# XbusTCO_smd.net
KiCad netlist of a schematic drawn in EAGLE
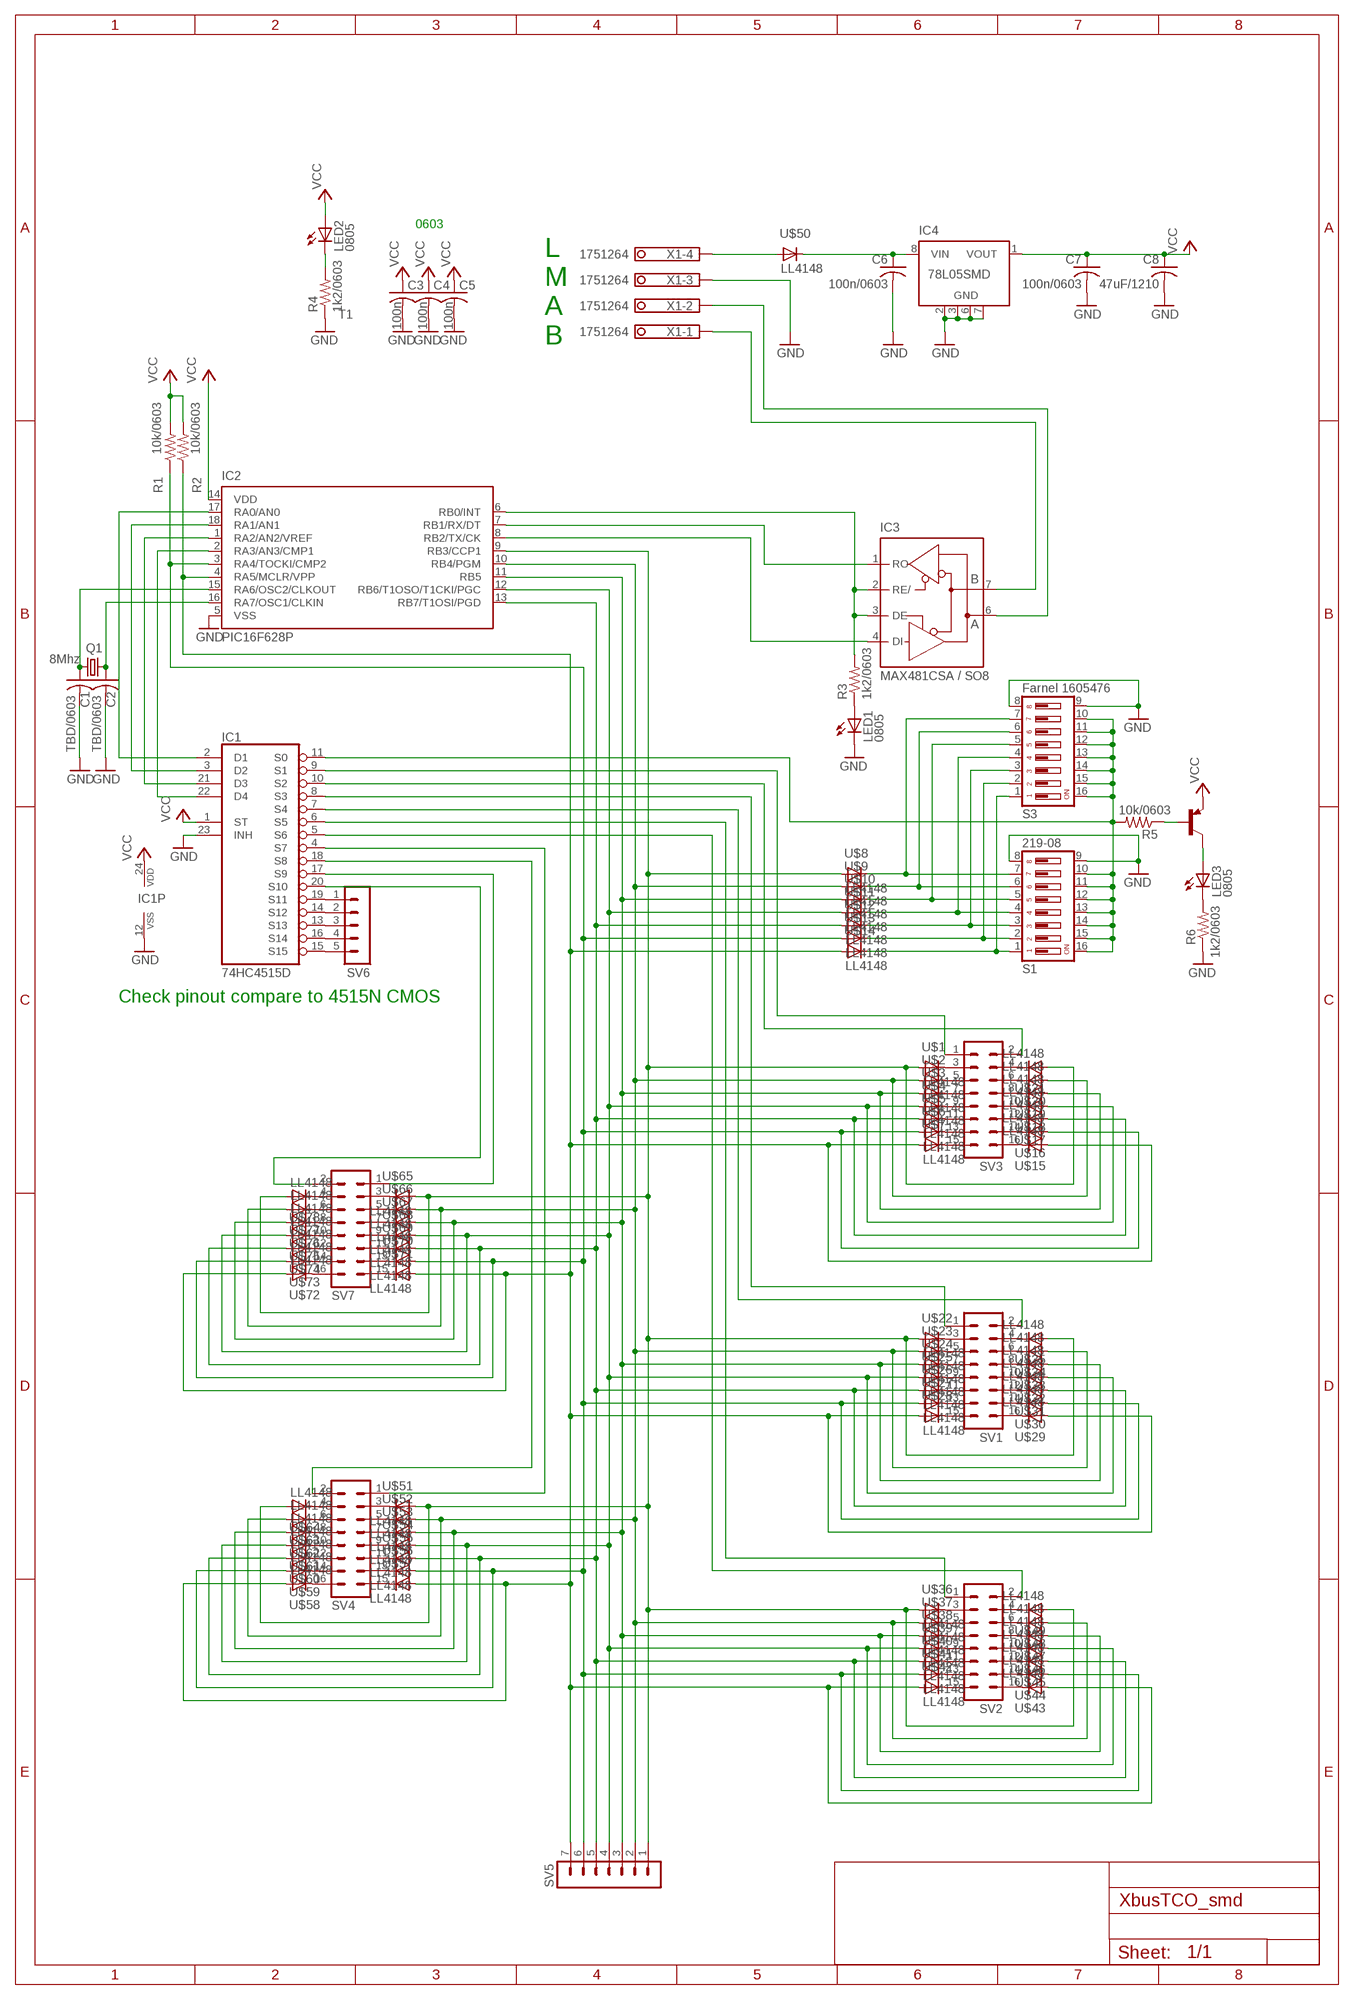
[diagram p0: schematic, sheet 1]

(export (version "E")
  (design (tool "Eeschema 10.0.6"))
  (components
    (comp (ref "C1")
      (value "TBD/0603")
      (footprint "eagle-import:C0603")
      (libsource (lib "eagle-import") (part "C-USC0603"))
    )
    (comp (ref "C2")
      (value "TBD/0603")
      (footprint "eagle-import:C0603")
      (libsource (lib "eagle-import") (part "C-USC0603"))
    )
    (comp (ref "C3")
      (value "100n")
      (footprint "eagle-import:C0603")
      (libsource (lib "eagle-import") (part "C-USC0603"))
    )
    (comp (ref "C4")
      (value "100n")
      (footprint "eagle-import:C0603")
      (libsource (lib "eagle-import") (part "C-USC0603"))
    )
    (comp (ref "C5")
      (value "100n")
      (footprint "eagle-import:C0603")
      (libsource (lib "eagle-import") (part "C-USC0603"))
    )
    (comp (ref "C6")
      (value "100n/0603")
      (footprint "eagle-import:C0603")
      (libsource (lib "eagle-import") (part "C-USC0603"))
    )
    (comp (ref "C7")
      (value "100n/0603")
      (footprint "eagle-import:C0603")
      (libsource (lib "eagle-import") (part "C-USC0603"))
    )
    (comp (ref "C8")
      (value "47uF/1210")
      (footprint "eagle-import:C1210")
      (libsource (lib "eagle-import") (part "C-USC1210"))
    )
    (comp (ref "IC1")
      (value "74HC4515D")
      (footprint "eagle-import:SO24W")
      (libsource (lib "eagle-import") (part "4515D"))
    )
    (comp (ref "IC2")
      (value "PIC16F628P")
      (footprint "eagle-import:DIL18")
      (fields (field (name "MF") "MICROCHIP") (field (name "MPN") "PIC16F628-04I/P"))
      (libsource (lib "eagle-import") (part "PIC16F62P8"))
    )
    (comp (ref "IC3")
      (value "MAX481CSA / SO8")
      (footprint "eagle-import:SO08")
      (fields (field (name "MF") "MAXIM") (field (name "MPN") "MAX481CSA"))
      (libsource (lib "eagle-import") (part "MAX481CSA"))
    )
    (comp (ref "IC4")
      (value "78L05SMD")
      (footprint "eagle-import:SO08")
      (libsource (lib "eagle-import") (part "78LSMD05"))
    )
    (comp (ref "LED1")
      (value "0805")
      (footprint "eagle-import:CHIPLED_0805")
      (libsource (lib "eagle-import") (part "LEDCHIPLED_0805"))
    )
    (comp (ref "LED2")
      (value "0805")
      (footprint "eagle-import:CHIPLED_0805")
      (libsource (lib "eagle-import") (part "LEDCHIPLED_0805"))
    )
    (comp (ref "LED3")
      (value "0805")
      (footprint "eagle-import:CHIPLED_0805")
      (libsource (lib "eagle-import") (part "LEDCHIPLED_0805"))
    )
    (comp (ref "Q1")
      (value "8Mhz")
      (footprint "eagle-import:HC49U70")
      (libsource (lib "eagle-import") (part "CRYSTALHC49U70"))
    )
    (comp (ref "R1")
      (value "10k/0603")
      (footprint "eagle-import:R0603")
      (libsource (lib "eagle-import") (part "R-US_R0603"))
    )
    (comp (ref "R2")
      (value "10k/0603")
      (footprint "eagle-import:R0603")
      (libsource (lib "eagle-import") (part "R-US_R0603"))
    )
    (comp (ref "R3")
      (value "1k2/0603")
      (footprint "eagle-import:R0603")
      (libsource (lib "eagle-import") (part "R-US_R0603"))
    )
    (comp (ref "R4")
      (value "1k2/0603")
      (footprint "eagle-import:R0603")
      (libsource (lib "eagle-import") (part "R-US_R0603"))
    )
    (comp (ref "R5")
      (value "10k/0603")
      (footprint "eagle-import:R0603")
      (libsource (lib "eagle-import") (part "R-US_R0603"))
    )
    (comp (ref "R6")
      (value "1k2/0603")
      (footprint "eagle-import:R0603")
      (libsource (lib "eagle-import") (part "R-US_R0603"))
    )
    (comp (ref "S1")
      (value "219-08")
      (footprint "eagle-import:CTS-219-08")
      (libsource (lib "eagle-import") (part "219-08"))
    )
    (comp (ref "S3")
      (value "Farnel 1605476")
      (footprint "eagle-import:CTS-219-08J")
      (libsource (lib "eagle-import") (part "219-08J"))
    )
    (comp (ref "SV1")
      (value "MA08-2W")
      (footprint "eagle-import:MA08-2W")
      (libsource (lib "eagle-import") (part "MA08-2W"))
    )
    (comp (ref "SV2")
      (value "MA08-2W")
      (footprint "eagle-import:MA08-2W")
      (libsource (lib "eagle-import") (part "MA08-2W"))
    )
    (comp (ref "SV3")
      (value "MA08-2W")
      (footprint "eagle-import:MA08-2W")
      (libsource (lib "eagle-import") (part "MA08-2W"))
    )
    (comp (ref "SV4")
      (value "MA08-2W")
      (footprint "eagle-import:MA08-2W")
      (libsource (lib "eagle-import") (part "MA08-2W"))
    )
    (comp (ref "SV5")
      (value "MA07-1")
      (footprint "eagle-import:MA07-1")
      (libsource (lib "eagle-import") (part "MA07-1"))
    )
    (comp (ref "SV6")
      (value "MA05-1")
      (footprint "eagle-import:MA05-1")
      (libsource (lib "eagle-import") (part "MA05-1"))
    )
    (comp (ref "SV7")
      (value "MA08-2W")
      (footprint "eagle-import:MA08-2W")
      (libsource (lib "eagle-import") (part "MA08-2W"))
    )
    (comp (ref "T1")
      (value "BC857A-PNP-SOT23-BEC")
      (footprint "eagle-import:SOT23-BEC")
      (libsource (lib "eagle-import") (part "-PNP-SOT23-BECBC857A"))
    )
    (comp (ref "U$1")
      (value "LL4148")
      (footprint "eagle-import:MINIMELF")
      (fields (field (name "MF") "ON Semiconductor"))
      (libsource (lib "eagle-import") (part "LL4148"))
    )
    (comp (ref "U$2")
      (value "LL4148")
      (footprint "eagle-import:MINIMELF")
      (fields (field (name "MF") "ON Semiconductor"))
      (libsource (lib "eagle-import") (part "LL4148"))
    )
    (comp (ref "U$3")
      (value "LL4148")
      (footprint "eagle-import:MINIMELF")
      (fields (field (name "MF") "ON Semiconductor"))
      (libsource (lib "eagle-import") (part "LL4148"))
    )
    (comp (ref "U$4")
      (value "LL4148")
      (footprint "eagle-import:MINIMELF")
      (fields (field (name "MF") "ON Semiconductor"))
      (libsource (lib "eagle-import") (part "LL4148"))
    )
    (comp (ref "U$5")
      (value "LL4148")
      (footprint "eagle-import:MINIMELF")
      (fields (field (name "MF") "ON Semiconductor"))
      (libsource (lib "eagle-import") (part "LL4148"))
    )
    (comp (ref "U$6")
      (value "LL4148")
      (footprint "eagle-import:MINIMELF")
      (fields (field (name "MF") "ON Semiconductor"))
      (libsource (lib "eagle-import") (part "LL4148"))
    )
    (comp (ref "U$7")
      (value "LL4148")
      (footprint "eagle-import:MINIMELF")
      (fields (field (name "MF") "ON Semiconductor"))
      (libsource (lib "eagle-import") (part "LL4148"))
    )
    (comp (ref "U$8")
      (value "LL4148")
      (footprint "eagle-import:MINIMELF")
      (fields (field (name "MF") "ON Semiconductor"))
      (libsource (lib "eagle-import") (part "LL4148"))
    )
    (comp (ref "U$9")
      (value "LL4148")
      (footprint "eagle-import:MINIMELF")
      (fields (field (name "MF") "ON Semiconductor"))
      (libsource (lib "eagle-import") (part "LL4148"))
    )
    (comp (ref "U$10")
      (value "LL4148")
      (footprint "eagle-import:MINIMELF")
      (fields (field (name "MF") "ON Semiconductor"))
      (libsource (lib "eagle-import") (part "LL4148"))
    )
    (comp (ref "U$11")
      (value "LL4148")
      (footprint "eagle-import:MINIMELF")
      (fields (field (name "MF") "ON Semiconductor"))
      (libsource (lib "eagle-import") (part "LL4148"))
    )
    (comp (ref "U$12")
      (value "LL4148")
      (footprint "eagle-import:MINIMELF")
      (fields (field (name "MF") "ON Semiconductor"))
      (libsource (lib "eagle-import") (part "LL4148"))
    )
    (comp (ref "U$13")
      (value "LL4148")
      (footprint "eagle-import:MINIMELF")
      (fields (field (name "MF") "ON Semiconductor"))
      (libsource (lib "eagle-import") (part "LL4148"))
    )
    (comp (ref "U$14")
      (value "LL4148")
      (footprint "eagle-import:MINIMELF")
      (fields (field (name "MF") "ON Semiconductor"))
      (libsource (lib "eagle-import") (part "LL4148"))
    )
    (comp (ref "U$15")
      (value "LL4148")
      (footprint "eagle-import:MINIMELF")
      (fields (field (name "MF") "ON Semiconductor"))
      (libsource (lib "eagle-import") (part "LL4148"))
    )
    (comp (ref "U$16")
      (value "LL4148")
      (footprint "eagle-import:MINIMELF")
      (fields (field (name "MF") "ON Semiconductor"))
      (libsource (lib "eagle-import") (part "LL4148"))
    )
    (comp (ref "U$17")
      (value "LL4148")
      (footprint "eagle-import:MINIMELF")
      (fields (field (name "MF") "ON Semiconductor"))
      (libsource (lib "eagle-import") (part "LL4148"))
    )
    (comp (ref "U$18")
      (value "LL4148")
      (footprint "eagle-import:MINIMELF")
      (fields (field (name "MF") "ON Semiconductor"))
      (libsource (lib "eagle-import") (part "LL4148"))
    )
    (comp (ref "U$19")
      (value "LL4148")
      (footprint "eagle-import:MINIMELF")
      (fields (field (name "MF") "ON Semiconductor"))
      (libsource (lib "eagle-import") (part "LL4148"))
    )
    (comp (ref "U$20")
      (value "LL4148")
      (footprint "eagle-import:MINIMELF")
      (fields (field (name "MF") "ON Semiconductor"))
      (libsource (lib "eagle-import") (part "LL4148"))
    )
    (comp (ref "U$21")
      (value "LL4148")
      (footprint "eagle-import:MINIMELF")
      (fields (field (name "MF") "ON Semiconductor"))
      (libsource (lib "eagle-import") (part "LL4148"))
    )
    (comp (ref "U$22")
      (value "LL4148")
      (footprint "eagle-import:MINIMELF")
      (fields (field (name "MF") "ON Semiconductor"))
      (libsource (lib "eagle-import") (part "LL4148"))
    )
    (comp (ref "U$23")
      (value "LL4148")
      (footprint "eagle-import:MINIMELF")
      (fields (field (name "MF") "ON Semiconductor"))
      (libsource (lib "eagle-import") (part "LL4148"))
    )
    (comp (ref "U$24")
      (value "LL4148")
      (footprint "eagle-import:MINIMELF")
      (fields (field (name "MF") "ON Semiconductor"))
      (libsource (lib "eagle-import") (part "LL4148"))
    )
    (comp (ref "U$25")
      (value "LL4148")
      (footprint "eagle-import:MINIMELF")
      (fields (field (name "MF") "ON Semiconductor"))
      (libsource (lib "eagle-import") (part "LL4148"))
    )
    (comp (ref "U$26")
      (value "LL4148")
      (footprint "eagle-import:MINIMELF")
      (fields (field (name "MF") "ON Semiconductor"))
      (libsource (lib "eagle-import") (part "LL4148"))
    )
    (comp (ref "U$27")
      (value "LL4148")
      (footprint "eagle-import:MINIMELF")
      (fields (field (name "MF") "ON Semiconductor"))
      (libsource (lib "eagle-import") (part "LL4148"))
    )
    (comp (ref "U$28")
      (value "LL4148")
      (footprint "eagle-import:MINIMELF")
      (fields (field (name "MF") "ON Semiconductor"))
      (libsource (lib "eagle-import") (part "LL4148"))
    )
    (comp (ref "U$29")
      (value "LL4148")
      (footprint "eagle-import:MINIMELF")
      (fields (field (name "MF") "ON Semiconductor"))
      (libsource (lib "eagle-import") (part "LL4148"))
    )
    (comp (ref "U$30")
      (value "LL4148")
      (footprint "eagle-import:MINIMELF")
      (fields (field (name "MF") "ON Semiconductor"))
      (libsource (lib "eagle-import") (part "LL4148"))
    )
    (comp (ref "U$31")
      (value "LL4148")
      (footprint "eagle-import:MINIMELF")
      (fields (field (name "MF") "ON Semiconductor"))
      (libsource (lib "eagle-import") (part "LL4148"))
    )
    (comp (ref "U$32")
      (value "LL4148")
      (footprint "eagle-import:MINIMELF")
      (fields (field (name "MF") "ON Semiconductor"))
      (libsource (lib "eagle-import") (part "LL4148"))
    )
    (comp (ref "U$33")
      (value "LL4148")
      (footprint "eagle-import:MINIMELF")
      (fields (field (name "MF") "ON Semiconductor"))
      (libsource (lib "eagle-import") (part "LL4148"))
    )
    (comp (ref "U$34")
      (value "LL4148")
      (footprint "eagle-import:MINIMELF")
      (fields (field (name "MF") "ON Semiconductor"))
      (libsource (lib "eagle-import") (part "LL4148"))
    )
    (comp (ref "U$35")
      (value "LL4148")
      (footprint "eagle-import:MINIMELF")
      (fields (field (name "MF") "ON Semiconductor"))
      (libsource (lib "eagle-import") (part "LL4148"))
    )
    (comp (ref "U$36")
      (value "LL4148")
      (footprint "eagle-import:MINIMELF")
      (fields (field (name "MF") "ON Semiconductor"))
      (libsource (lib "eagle-import") (part "LL4148"))
    )
    (comp (ref "U$37")
      (value "LL4148")
      (footprint "eagle-import:MINIMELF")
      (fields (field (name "MF") "ON Semiconductor"))
      (libsource (lib "eagle-import") (part "LL4148"))
    )
    (comp (ref "U$38")
      (value "LL4148")
      (footprint "eagle-import:MINIMELF")
      (fields (field (name "MF") "ON Semiconductor"))
      (libsource (lib "eagle-import") (part "LL4148"))
    )
    (comp (ref "U$39")
      (value "LL4148")
      (footprint "eagle-import:MINIMELF")
      (fields (field (name "MF") "ON Semiconductor"))
      (libsource (lib "eagle-import") (part "LL4148"))
    )
    (comp (ref "U$40")
      (value "LL4148")
      (footprint "eagle-import:MINIMELF")
      (fields (field (name "MF") "ON Semiconductor"))
      (libsource (lib "eagle-import") (part "LL4148"))
    )
    (comp (ref "U$41")
      (value "LL4148")
      (footprint "eagle-import:MINIMELF")
      (fields (field (name "MF") "ON Semiconductor"))
      (libsource (lib "eagle-import") (part "LL4148"))
    )
    (comp (ref "U$42")
      (value "LL4148")
      (footprint "eagle-import:MINIMELF")
      (fields (field (name "MF") "ON Semiconductor"))
      (libsource (lib "eagle-import") (part "LL4148"))
    )
    (comp (ref "U$43")
      (value "LL4148")
      (footprint "eagle-import:MINIMELF")
      (fields (field (name "MF") "ON Semiconductor"))
      (libsource (lib "eagle-import") (part "LL4148"))
    )
    (comp (ref "U$44")
      (value "LL4148")
      (footprint "eagle-import:MINIMELF")
      (fields (field (name "MF") "ON Semiconductor"))
      (libsource (lib "eagle-import") (part "LL4148"))
    )
    (comp (ref "U$45")
      (value "LL4148")
      (footprint "eagle-import:MINIMELF")
      (fields (field (name "MF") "ON Semiconductor"))
      (libsource (lib "eagle-import") (part "LL4148"))
    )
    (comp (ref "U$46")
      (value "LL4148")
      (footprint "eagle-import:MINIMELF")
      (fields (field (name "MF") "ON Semiconductor"))
      (libsource (lib "eagle-import") (part "LL4148"))
    )
    (comp (ref "U$47")
      (value "LL4148")
      (footprint "eagle-import:MINIMELF")
      (fields (field (name "MF") "ON Semiconductor"))
      (libsource (lib "eagle-import") (part "LL4148"))
    )
    (comp (ref "U$48")
      (value "LL4148")
      (footprint "eagle-import:MINIMELF")
      (fields (field (name "MF") "ON Semiconductor"))
      (libsource (lib "eagle-import") (part "LL4148"))
    )
    (comp (ref "U$49")
      (value "LL4148")
      (footprint "eagle-import:MINIMELF")
      (fields (field (name "MF") "ON Semiconductor"))
      (libsource (lib "eagle-import") (part "LL4148"))
    )
    (comp (ref "U$50")
      (value "LL4148")
      (footprint "eagle-import:MINIMELF")
      (fields (field (name "MF") "ON Semiconductor"))
      (libsource (lib "eagle-import") (part "LL4148"))
    )
    (comp (ref "U$51")
      (value "LL4148")
      (footprint "eagle-import:MINIMELF")
      (fields (field (name "MF") "ON Semiconductor"))
      (libsource (lib "eagle-import") (part "LL4148"))
    )
    (comp (ref "U$52")
      (value "LL4148")
      (footprint "eagle-import:MINIMELF")
      (fields (field (name "MF") "ON Semiconductor"))
      (libsource (lib "eagle-import") (part "LL4148"))
    )
    (comp (ref "U$53")
      (value "LL4148")
      (footprint "eagle-import:MINIMELF")
      (fields (field (name "MF") "ON Semiconductor"))
      (libsource (lib "eagle-import") (part "LL4148"))
    )
    (comp (ref "U$54")
      (value "LL4148")
      (footprint "eagle-import:MINIMELF")
      (fields (field (name "MF") "ON Semiconductor"))
      (libsource (lib "eagle-import") (part "LL4148"))
    )
    (comp (ref "U$55")
      (value "LL4148")
      (footprint "eagle-import:MINIMELF")
      (fields (field (name "MF") "ON Semiconductor"))
      (libsource (lib "eagle-import") (part "LL4148"))
    )
    (comp (ref "U$56")
      (value "LL4148")
      (footprint "eagle-import:MINIMELF")
      (fields (field (name "MF") "ON Semiconductor"))
      (libsource (lib "eagle-import") (part "LL4148"))
    )
    (comp (ref "U$57")
      (value "LL4148")
      (footprint "eagle-import:MINIMELF")
      (fields (field (name "MF") "ON Semiconductor"))
      (libsource (lib "eagle-import") (part "LL4148"))
    )
    (comp (ref "U$58")
      (value "LL4148")
      (footprint "eagle-import:MINIMELF")
      (fields (field (name "MF") "ON Semiconductor"))
      (libsource (lib "eagle-import") (part "LL4148"))
    )
    (comp (ref "U$59")
      (value "LL4148")
      (footprint "eagle-import:MINIMELF")
      (fields (field (name "MF") "ON Semiconductor"))
      (libsource (lib "eagle-import") (part "LL4148"))
    )
    (comp (ref "U$60")
      (value "LL4148")
      (footprint "eagle-import:MINIMELF")
      (fields (field (name "MF") "ON Semiconductor"))
      (libsource (lib "eagle-import") (part "LL4148"))
    )
    (comp (ref "U$61")
      (value "LL4148")
      (footprint "eagle-import:MINIMELF")
      (fields (field (name "MF") "ON Semiconductor"))
      (libsource (lib "eagle-import") (part "LL4148"))
    )
    (comp (ref "U$62")
      (value "LL4148")
      (footprint "eagle-import:MINIMELF")
      (fields (field (name "MF") "ON Semiconductor"))
      (libsource (lib "eagle-import") (part "LL4148"))
    )
    (comp (ref "U$63")
      (value "LL4148")
      (footprint "eagle-import:MINIMELF")
      (fields (field (name "MF") "ON Semiconductor"))
      (libsource (lib "eagle-import") (part "LL4148"))
    )
    (comp (ref "U$64")
      (value "LL4148")
      (footprint "eagle-import:MINIMELF")
      (fields (field (name "MF") "ON Semiconductor"))
      (libsource (lib "eagle-import") (part "LL4148"))
    )
    (comp (ref "U$65")
      (value "LL4148")
      (footprint "eagle-import:MINIMELF")
      (fields (field (name "MF") "ON Semiconductor"))
      (libsource (lib "eagle-import") (part "LL4148"))
    )
    (comp (ref "U$66")
      (value "LL4148")
      (footprint "eagle-import:MINIMELF")
      (fields (field (name "MF") "ON Semiconductor"))
      (libsource (lib "eagle-import") (part "LL4148"))
    )
    (comp (ref "U$67")
      (value "LL4148")
      (footprint "eagle-import:MINIMELF")
      (fields (field (name "MF") "ON Semiconductor"))
      (libsource (lib "eagle-import") (part "LL4148"))
    )
    (comp (ref "U$68")
      (value "LL4148")
      (footprint "eagle-import:MINIMELF")
      (fields (field (name "MF") "ON Semiconductor"))
      (libsource (lib "eagle-import") (part "LL4148"))
    )
    (comp (ref "U$69")
      (value "LL4148")
      (footprint "eagle-import:MINIMELF")
      (fields (field (name "MF") "ON Semiconductor"))
      (libsource (lib "eagle-import") (part "LL4148"))
    )
    (comp (ref "U$70")
      (value "LL4148")
      (footprint "eagle-import:MINIMELF")
      (fields (field (name "MF") "ON Semiconductor"))
      (libsource (lib "eagle-import") (part "LL4148"))
    )
    (comp (ref "U$71")
      (value "LL4148")
      (footprint "eagle-import:MINIMELF")
      (fields (field (name "MF") "ON Semiconductor"))
      (libsource (lib "eagle-import") (part "LL4148"))
    )
    (comp (ref "U$72")
      (value "LL4148")
      (footprint "eagle-import:MINIMELF")
      (fields (field (name "MF") "ON Semiconductor"))
      (libsource (lib "eagle-import") (part "LL4148"))
    )
    (comp (ref "U$73")
      (value "LL4148")
      (footprint "eagle-import:MINIMELF")
      (fields (field (name "MF") "ON Semiconductor"))
      (libsource (lib "eagle-import") (part "LL4148"))
    )
    (comp (ref "U$74")
      (value "LL4148")
      (footprint "eagle-import:MINIMELF")
      (fields (field (name "MF") "ON Semiconductor"))
      (libsource (lib "eagle-import") (part "LL4148"))
    )
    (comp (ref "U$75")
      (value "LL4148")
      (footprint "eagle-import:MINIMELF")
      (fields (field (name "MF") "ON Semiconductor"))
      (libsource (lib "eagle-import") (part "LL4148"))
    )
    (comp (ref "U$76")
      (value "LL4148")
      (footprint "eagle-import:MINIMELF")
      (fields (field (name "MF") "ON Semiconductor"))
      (libsource (lib "eagle-import") (part "LL4148"))
    )
    (comp (ref "U$77")
      (value "LL4148")
      (footprint "eagle-import:MINIMELF")
      (fields (field (name "MF") "ON Semiconductor"))
      (libsource (lib "eagle-import") (part "LL4148"))
    )
    (comp (ref "U$78")
      (value "LL4148")
      (footprint "eagle-import:MINIMELF")
      (fields (field (name "MF") "ON Semiconductor"))
      (libsource (lib "eagle-import") (part "LL4148"))
    )
    (comp (ref "X1")
      (value "1751264")
      (footprint "eagle-import:1751264")
      (libsource (lib "eagle-import") (part "1751264"))
    )
  )
  (nets
    (net (code "1") (name "GND") (class "Default")
      (node (ref "C1") (pin "2") (pinfunction "2_2") (pintype "passive"))
      (node (ref "C2") (pin "2") (pinfunction "2_2") (pintype "passive"))
      (node (ref "C3") (pin "2") (pinfunction "2_2") (pintype "passive"))
      (node (ref "C4") (pin "2") (pinfunction "2_2") (pintype "passive"))
      (node (ref "C5") (pin "2") (pinfunction "2_2") (pintype "passive"))
      (node (ref "C6") (pin "2") (pinfunction "2_2") (pintype "passive"))
      (node (ref "C7") (pin "2") (pinfunction "2_2") (pintype "passive"))
      (node (ref "C8") (pin "2") (pinfunction "2_2") (pintype "passive"))
      (node (ref "IC1") (pin "12") (pinfunction "VSS_12") (pintype "power_in"))
      (node (ref "IC1") (pin "23") (pinfunction "INH_23") (pintype "input"))
      (node (ref "IC2") (pin "5") (pinfunction "VSS_5") (pintype "power_in"))
      (node (ref "IC4") (pin "2") (pinfunction "GND_2") (pintype "power_in"))
      (node (ref "IC4") (pin "3") (pinfunction "GND_3") (pintype "power_in"))
      (node (ref "IC4") (pin "6") (pinfunction "GND_6") (pintype "power_in"))
      (node (ref "IC4") (pin "7") (pinfunction "GND_7") (pintype "power_in"))
      (node (ref "LED1") (pin "C") (pinfunction "C_C") (pintype "passive"))
      (node (ref "R4") (pin "1") (pinfunction "1_1") (pintype "passive"))
      (node (ref "R6") (pin "1") (pinfunction "1_1") (pintype "passive"))
      (node (ref "S1") (pin "8") (pinfunction "8_8") (pintype "passive"))
      (node (ref "S1") (pin "9") (pinfunction "9_9") (pintype "passive"))
      (node (ref "S3") (pin "8") (pinfunction "8_8") (pintype "passive"))
      (node (ref "S3") (pin "9") (pinfunction "9_9") (pintype "passive"))
      (node (ref "X1") (pin "3") (pinfunction "K_3") (pintype "passive"))
    )
    (net (code "2") (name "Net-(IC1A-D1)") (class "Default")
      (node (ref "IC1") (pin "2") (pinfunction "D1_2") (pintype "input"))
      (node (ref "IC2") (pin "17") (pinfunction "RA0/AN0_17") (pintype "bidirectional"))
    )
    (net (code "3") (name "Net-(IC1A-D2)") (class "Default")
      (node (ref "IC1") (pin "3") (pinfunction "D2_3") (pintype "input"))
      (node (ref "IC2") (pin "18") (pinfunction "RA1/AN1_18") (pintype "bidirectional"))
    )
    (net (code "4") (name "Net-(IC1A-D3)") (class "Default")
      (node (ref "IC1") (pin "21") (pinfunction "D3_21") (pintype "input"))
      (node (ref "IC2") (pin "1") (pinfunction "RA2/AN2/VREF_1") (pintype "bidirectional"))
    )
    (net (code "5") (name "Net-(IC1A-D4)") (class "Default")
      (node (ref "IC1") (pin "22") (pinfunction "D4_22") (pintype "input"))
      (node (ref "IC2") (pin "2") (pinfunction "RA3/AN3/CMP1_2") (pintype "bidirectional"))
    )
    (net (code "6") (name "Net-(IC1A-S0)") (class "Default")
      (node (ref "IC1") (pin "11") (pinfunction "S0_11") (pintype "output"))
      (node (ref "R5") (pin "2") (pinfunction "2_2") (pintype "passive"))
      (node (ref "S1") (pin "10") (pinfunction "10_10") (pintype "passive"))
      (node (ref "S1") (pin "11") (pinfunction "11_11") (pintype "passive"))
      (node (ref "S1") (pin "12") (pinfunction "12_12") (pintype "passive"))
      (node (ref "S1") (pin "13") (pinfunction "13_13") (pintype "passive"))
      (node (ref "S1") (pin "14") (pinfunction "14_14") (pintype "passive"))
      (node (ref "S1") (pin "15") (pinfunction "15_15") (pintype "passive"))
      (node (ref "S1") (pin "16") (pinfunction "16_16") (pintype "passive"))
      (node (ref "S3") (pin "10") (pinfunction "10_10") (pintype "passive"))
      (node (ref "S3") (pin "11") (pinfunction "11_11") (pintype "passive"))
      (node (ref "S3") (pin "12") (pinfunction "12_12") (pintype "passive"))
      (node (ref "S3") (pin "13") (pinfunction "13_13") (pintype "passive"))
      (node (ref "S3") (pin "14") (pinfunction "14_14") (pintype "passive"))
      (node (ref "S3") (pin "15") (pinfunction "15_15") (pintype "passive"))
      (node (ref "S3") (pin "16") (pinfunction "16_16") (pintype "passive"))
    )
    (net (code "7") (name "Net-(IC1A-S1)") (class "Default")
      (node (ref "IC1") (pin "9") (pinfunction "S1_9") (pintype "output"))
      (node (ref "SV3") (pin "1") (pinfunction "1_1") (pintype "passive"))
    )
    (net (code "8") (name "Net-(IC1A-S2)") (class "Default")
      (node (ref "IC1") (pin "10") (pinfunction "S2_10") (pintype "output"))
      (node (ref "SV3") (pin "2") (pinfunction "2_2") (pintype "passive"))
    )
    (net (code "9") (name "Net-(IC1A-S3)") (class "Default")
      (node (ref "IC1") (pin "8") (pinfunction "S3_8") (pintype "output"))
      (node (ref "SV1") (pin "1") (pinfunction "1_1") (pintype "passive"))
    )
    (net (code "10") (name "Net-(IC1A-S4)") (class "Default")
      (node (ref "IC1") (pin "7") (pinfunction "S4_7") (pintype "output"))
      (node (ref "SV1") (pin "2") (pinfunction "2_2") (pintype "passive"))
    )
    (net (code "11") (name "Net-(IC1A-S5)") (class "Default")
      (node (ref "IC1") (pin "6") (pinfunction "S5_6") (pintype "output"))
      (node (ref "SV2") (pin "1") (pinfunction "1_1") (pintype "passive"))
    )
    (net (code "12") (name "Net-(IC1A-S6)") (class "Default")
      (node (ref "IC1") (pin "5") (pinfunction "S6_5") (pintype "output"))
      (node (ref "SV2") (pin "2") (pinfunction "2_2") (pintype "passive"))
    )
    (net (code "13") (name "Net-(IC1A-S7)") (class "Default")
      (node (ref "IC1") (pin "4") (pinfunction "S7_4") (pintype "output"))
      (node (ref "SV4") (pin "1") (pinfunction "1_1") (pintype "passive"))
    )
    (net (code "14") (name "Net-(IC1A-S8)") (class "Default")
      (node (ref "IC1") (pin "18") (pinfunction "S8_18") (pintype "output"))
      (node (ref "SV4") (pin "2") (pinfunction "2_2") (pintype "passive"))
    )
    (net (code "15") (name "Net-(IC1A-S9)") (class "Default")
      (node (ref "IC1") (pin "17") (pinfunction "S9_17") (pintype "output"))
      (node (ref "SV7") (pin "1") (pinfunction "1_1") (pintype "passive"))
    )
    (net (code "16") (name "Net-(IC1A-S10)") (class "Default")
      (node (ref "IC1") (pin "20") (pinfunction "S10_20") (pintype "output"))
      (node (ref "SV7") (pin "2") (pinfunction "2_2") (pintype "passive"))
    )
    (net (code "17") (name "Net-(IC1A-S11)") (class "Default")
      (node (ref "IC1") (pin "19") (pinfunction "S11_19") (pintype "output"))
      (node (ref "SV6") (pin "1") (pinfunction "1_1") (pintype "passive"))
    )
    (net (code "18") (name "Net-(IC1A-S12)") (class "Default")
      (node (ref "IC1") (pin "14") (pinfunction "S12_14") (pintype "output"))
      (node (ref "SV6") (pin "2") (pinfunction "2_2") (pintype "passive"))
    )
    (net (code "19") (name "Net-(IC1A-S13)") (class "Default")
      (node (ref "IC1") (pin "13") (pinfunction "S13_13") (pintype "output"))
      (node (ref "SV6") (pin "3") (pinfunction "3_3") (pintype "passive"))
    )
    (net (code "20") (name "Net-(IC1A-S14)") (class "Default")
      (node (ref "IC1") (pin "16") (pinfunction "S14_16") (pintype "output"))
      (node (ref "SV6") (pin "4") (pinfunction "4_4") (pintype "passive"))
    )
    (net (code "21") (name "Net-(IC1A-S15)") (class "Default")
      (node (ref "IC1") (pin "15") (pinfunction "S15_15") (pintype "output"))
      (node (ref "SV6") (pin "5") (pinfunction "5_5") (pintype "passive"))
    )
    (net (code "22") (name "Net-(IC2-RA4{slash}TOCKI{slash}CMP2)") (class "Default")
      (node (ref "IC2") (pin "3") (pinfunction "RA4/TOCKI/CMP2_3") (pintype "bidirectional"))
      (node (ref "R1") (pin "1") (pinfunction "1_1") (pintype "passive"))
      (node (ref "SV5") (pin "6") (pinfunction "6_6") (pintype "passive"))
      (node (ref "U$13") (pin "A") (pinfunction "A_A") (pintype "passive"))
      (node (ref "U$16") (pin "A") (pinfunction "A_A") (pintype "passive"))
      (node (ref "U$27") (pin "A") (pinfunction "A_A") (pintype "passive"))
      (node (ref "U$30") (pin "A") (pinfunction "A_A") (pintype "passive"))
      (node (ref "U$41") (pin "A") (pinfunction "A_A") (pintype "passive"))
      (node (ref "U$44") (pin "A") (pinfunction "A_A") (pintype "passive"))
      (node (ref "U$56") (pin "A") (pinfunction "A_A") (pintype "passive"))
      (node (ref "U$59") (pin "A") (pinfunction "A_A") (pintype "passive"))
      (node (ref "U$6") (pin "A") (pinfunction "A_A") (pintype "passive"))
      (node (ref "U$70") (pin "A") (pinfunction "A_A") (pintype "passive"))
      (node (ref "U$73") (pin "A") (pinfunction "A_A") (pintype "passive"))
    )
    (net (code "23") (name "Net-(IC2-RA5{slash}MCLR{slash}VPP)") (class "Default")
      (node (ref "IC2") (pin "4") (pinfunction "RA5/MCLR/VPP_4") (pintype "bidirectional"))
      (node (ref "R2") (pin "1") (pinfunction "1_1") (pintype "passive"))
      (node (ref "SV5") (pin "7") (pinfunction "7_7") (pintype "passive"))
      (node (ref "U$14") (pin "A") (pinfunction "A_A") (pintype "passive"))
      (node (ref "U$15") (pin "A") (pinfunction "A_A") (pintype "passive"))
      (node (ref "U$28") (pin "A") (pinfunction "A_A") (pintype "passive"))
      (node (ref "U$29") (pin "A") (pinfunction "A_A") (pintype "passive"))
      (node (ref "U$42") (pin "A") (pinfunction "A_A") (pintype "passive"))
      (node (ref "U$43") (pin "A") (pinfunction "A_A") (pintype "passive"))
      (node (ref "U$57") (pin "A") (pinfunction "A_A") (pintype "passive"))
      (node (ref "U$58") (pin "A") (pinfunction "A_A") (pintype "passive"))
      (node (ref "U$7") (pin "A") (pinfunction "A_A") (pintype "passive"))
      (node (ref "U$71") (pin "A") (pinfunction "A_A") (pintype "passive"))
      (node (ref "U$72") (pin "A") (pinfunction "A_A") (pintype "passive"))
    )
    (net (code "24") (name "Net-(IC2-RA6{slash}OSC2{slash}CLKOUT)") (class "Default")
      (node (ref "C1") (pin "1") (pinfunction "1_1") (pintype "passive"))
      (node (ref "IC2") (pin "15") (pinfunction "RA6/OSC2/CLKOUT_15") (pintype "bidirectional"))
      (node (ref "Q1") (pin "2") (pinfunction "2_2") (pintype "passive"))
    )
    (net (code "25") (name "Net-(IC2-RA7{slash}OSC1{slash}CLKIN)") (class "Default")
      (node (ref "C2") (pin "1") (pinfunction "1_1") (pintype "passive"))
      (node (ref "IC2") (pin "16") (pinfunction "RA7/OSC1/CLKIN_16") (pintype "bidirectional"))
      (node (ref "Q1") (pin "1") (pinfunction "1_1") (pintype "passive"))
    )
    (net (code "26") (name "Net-(IC2-RB0{slash}INT)") (class "Default")
      (node (ref "IC2") (pin "6") (pinfunction "RB0/INT_6") (pintype "bidirectional"))
      (node (ref "IC3") (pin "2") (pinfunction "RE/_2") (pintype "input"))
      (node (ref "IC3") (pin "3") (pinfunction "DE_3") (pintype "input"))
      (node (ref "R3") (pin "2") (pinfunction "2_2") (pintype "passive"))
    )
    (net (code "27") (name "Net-(IC2-RB1{slash}RX{slash}DT)") (class "Default")
      (node (ref "IC2") (pin "7") (pinfunction "RB1/RX/DT_7") (pintype "bidirectional"))
      (node (ref "IC3") (pin "1") (pinfunction "RO_1") (pintype "output"))
    )
    (net (code "28") (name "Net-(IC2-RB2{slash}TX{slash}CK)") (class "Default")
      (node (ref "IC2") (pin "8") (pinfunction "RB2/TX/CK_8") (pintype "bidirectional"))
      (node (ref "IC3") (pin "4") (pinfunction "DI_4") (pintype "input"))
    )
    (net (code "29") (name "Net-(IC2-RB3{slash}CCP1)") (class "Default")
      (node (ref "IC2") (pin "9") (pinfunction "RB3/CCP1_9") (pintype "bidirectional"))
      (node (ref "SV5") (pin "1") (pinfunction "1_1") (pintype "passive"))
      (node (ref "U$1") (pin "A") (pinfunction "A_A") (pintype "passive"))
      (node (ref "U$21") (pin "A") (pinfunction "A_A") (pintype "passive"))
      (node (ref "U$22") (pin "A") (pinfunction "A_A") (pintype "passive"))
      (node (ref "U$35") (pin "A") (pinfunction "A_A") (pintype "passive"))
      (node (ref "U$36") (pin "A") (pinfunction "A_A") (pintype "passive"))
      (node (ref "U$49") (pin "A") (pinfunction "A_A") (pintype "passive"))
      (node (ref "U$51") (pin "A") (pinfunction "A_A") (pintype "passive"))
      (node (ref "U$64") (pin "A") (pinfunction "A_A") (pintype "passive"))
      (node (ref "U$65") (pin "A") (pinfunction "A_A") (pintype "passive"))
      (node (ref "U$78") (pin "A") (pinfunction "A_A") (pintype "passive"))
      (node (ref "U$8") (pin "A") (pinfunction "A_A") (pintype "passive"))
    )
    (net (code "30") (name "Net-(IC2-RB4{slash}PGM)") (class "Default")
      (node (ref "IC2") (pin "10") (pinfunction "RB4/PGM_10") (pintype "bidirectional"))
      (node (ref "SV5") (pin "2") (pinfunction "2_2") (pintype "passive"))
      (node (ref "U$2") (pin "A") (pinfunction "A_A") (pintype "passive"))
      (node (ref "U$20") (pin "A") (pinfunction "A_A") (pintype "passive"))
      (node (ref "U$23") (pin "A") (pinfunction "A_A") (pintype "passive"))
      (node (ref "U$34") (pin "A") (pinfunction "A_A") (pintype "passive"))
      (node (ref "U$37") (pin "A") (pinfunction "A_A") (pintype "passive"))
      (node (ref "U$48") (pin "A") (pinfunction "A_A") (pintype "passive"))
      (node (ref "U$52") (pin "A") (pinfunction "A_A") (pintype "passive"))
      (node (ref "U$63") (pin "A") (pinfunction "A_A") (pintype "passive"))
      (node (ref "U$66") (pin "A") (pinfunction "A_A") (pintype "passive"))
      (node (ref "U$77") (pin "A") (pinfunction "A_A") (pintype "passive"))
      (node (ref "U$9") (pin "A") (pinfunction "A_A") (pintype "passive"))
    )
    (net (code "31") (name "Net-(IC2-RB5)") (class "Default")
      (node (ref "IC2") (pin "11") (pinfunction "RB5_11") (pintype "bidirectional"))
      (node (ref "SV5") (pin "3") (pinfunction "3_3") (pintype "passive"))
      (node (ref "U$10") (pin "A") (pinfunction "A_A") (pintype "passive"))
      (node (ref "U$19") (pin "A") (pinfunction "A_A") (pintype "passive"))
      (node (ref "U$24") (pin "A") (pinfunction "A_A") (pintype "passive"))
      (node (ref "U$3") (pin "A") (pinfunction "A_A") (pintype "passive"))
      (node (ref "U$33") (pin "A") (pinfunction "A_A") (pintype "passive"))
      (node (ref "U$38") (pin "A") (pinfunction "A_A") (pintype "passive"))
      (node (ref "U$47") (pin "A") (pinfunction "A_A") (pintype "passive"))
      (node (ref "U$53") (pin "A") (pinfunction "A_A") (pintype "passive"))
      (node (ref "U$62") (pin "A") (pinfunction "A_A") (pintype "passive"))
      (node (ref "U$67") (pin "A") (pinfunction "A_A") (pintype "passive"))
      (node (ref "U$76") (pin "A") (pinfunction "A_A") (pintype "passive"))
    )
    (net (code "32") (name "Net-(IC2-RB6{slash}T1OSO{slash}T1CKI{slash}PGC)") (class "Default")
      (node (ref "IC2") (pin "12") (pinfunction "RB6/T1OSO/T1CKI/PGC_12") (pintype "bidirectional"))
      (node (ref "SV5") (pin "4") (pinfunction "4_4") (pintype "passive"))
      (node (ref "U$11") (pin "A") (pinfunction "A_A") (pintype "passive"))
      (node (ref "U$18") (pin "A") (pinfunction "A_A") (pintype "passive"))
      (node (ref "U$25") (pin "A") (pinfunction "A_A") (pintype "passive"))
      (node (ref "U$32") (pin "A") (pinfunction "A_A") (pintype "passive"))
      (node (ref "U$39") (pin "A") (pinfunction "A_A") (pintype "passive"))
      (node (ref "U$4") (pin "A") (pinfunction "A_A") (pintype "passive"))
      (node (ref "U$46") (pin "A") (pinfunction "A_A") (pintype "passive"))
      (node (ref "U$54") (pin "A") (pinfunction "A_A") (pintype "passive"))
      (node (ref "U$61") (pin "A") (pinfunction "A_A") (pintype "passive"))
      (node (ref "U$68") (pin "A") (pinfunction "A_A") (pintype "passive"))
      (node (ref "U$75") (pin "A") (pinfunction "A_A") (pintype "passive"))
    )
    (net (code "33") (name "Net-(IC2-RB7{slash}T1OSI{slash}PGD)") (class "Default")
      (node (ref "IC2") (pin "13") (pinfunction "RB7/T1OSI/PGD_13") (pintype "bidirectional"))
      (node (ref "SV5") (pin "5") (pinfunction "5_5") (pintype "passive"))
      (node (ref "U$12") (pin "A") (pinfunction "A_A") (pintype "passive"))
      (node (ref "U$17") (pin "A") (pinfunction "A_A") (pintype "passive"))
      (node (ref "U$26") (pin "A") (pinfunction "A_A") (pintype "passive"))
      (node (ref "U$31") (pin "A") (pinfunction "A_A") (pintype "passive"))
      (node (ref "U$40") (pin "A") (pinfunction "A_A") (pintype "passive"))
      (node (ref "U$45") (pin "A") (pinfunction "A_A") (pintype "passive"))
      (node (ref "U$5") (pin "A") (pinfunction "A_A") (pintype "passive"))
      (node (ref "U$55") (pin "A") (pinfunction "A_A") (pintype "passive"))
      (node (ref "U$60") (pin "A") (pinfunction "A_A") (pintype "passive"))
      (node (ref "U$69") (pin "A") (pinfunction "A_A") (pintype "passive"))
      (node (ref "U$74") (pin "A") (pinfunction "A_A") (pintype "passive"))
    )
    (net (code "34") (name "Net-(IC3A-A)") (class "Default")
      (node (ref "IC3") (pin "6") (pinfunction "A_6") (pintype "passive"))
      (node (ref "X1") (pin "2") (pinfunction "K_2") (pintype "passive"))
    )
    (net (code "35") (name "Net-(IC3A-B)") (class "Default")
      (node (ref "IC3") (pin "7") (pinfunction "B_7") (pintype "passive"))
      (node (ref "X1") (pin "1") (pinfunction "K_1") (pintype "passive"))
    )
    (net (code "36") (name "Net-(IC4A-VIN)") (class "Default")
      (node (ref "C6") (pin "1") (pinfunction "1_1") (pintype "passive"))
      (node (ref "IC4") (pin "8") (pinfunction "VIN_8") (pintype "passive"))
      (node (ref "U$50") (pin "C") (pinfunction "C_C") (pintype "passive"))
    )
    (net (code "37") (name "Net-(LED1-PadA)") (class "Default")
      (node (ref "LED1") (pin "A") (pinfunction "A_A") (pintype "passive"))
      (node (ref "R3") (pin "1") (pinfunction "1_1") (pintype "passive"))
    )
    (net (code "38") (name "Net-(LED2-PadC)") (class "Default")
      (node (ref "LED2") (pin "C") (pinfunction "C_C") (pintype "passive"))
      (node (ref "R4") (pin "2") (pinfunction "2_2") (pintype "passive"))
    )
    (net (code "39") (name "Net-(LED3-PadA)") (class "Default")
      (node (ref "LED3") (pin "A") (pinfunction "A_A") (pintype "passive"))
      (node (ref "T1") (pin "C") (pinfunction "C_C") (pintype "passive"))
    )
    (net (code "40") (name "Net-(LED3-PadC)") (class "Default")
      (node (ref "LED3") (pin "C") (pinfunction "C_C") (pintype "passive"))
      (node (ref "R6") (pin "2") (pinfunction "2_2") (pintype "passive"))
    )
    (net (code "41") (name "Net-(R5-Pad1)") (class "Default")
      (node (ref "R5") (pin "1") (pinfunction "1_1") (pintype "passive"))
      (node (ref "T1") (pin "B") (pinfunction "B_B") (pintype "passive"))
    )
    (net (code "42") (name "Net-(S1-Pad1)") (class "Default")
      (node (ref "S1") (pin "1") (pinfunction "1_1") (pintype "passive"))
      (node (ref "S3") (pin "1") (pinfunction "1_1") (pintype "passive"))
      (node (ref "U$14") (pin "C") (pinfunction "C_C") (pintype "passive"))
    )
    (net (code "43") (name "Net-(S1-Pad2)") (class "Default")
      (node (ref "S1") (pin "2") (pinfunction "2_2") (pintype "passive"))
      (node (ref "S3") (pin "2") (pinfunction "2_2") (pintype "passive"))
      (node (ref "U$13") (pin "C") (pinfunction "C_C") (pintype "passive"))
    )
    (net (code "44") (name "Net-(S1-Pad3)") (class "Default")
      (node (ref "S1") (pin "3") (pinfunction "3_3") (pintype "passive"))
      (node (ref "S3") (pin "3") (pinfunction "3_3") (pintype "passive"))
      (node (ref "U$12") (pin "C") (pinfunction "C_C") (pintype "passive"))
    )
    (net (code "45") (name "Net-(S1-Pad4)") (class "Default")
      (node (ref "S1") (pin "4") (pinfunction "4_4") (pintype "passive"))
      (node (ref "S3") (pin "4") (pinfunction "4_4") (pintype "passive"))
      (node (ref "U$11") (pin "C") (pinfunction "C_C") (pintype "passive"))
    )
    (net (code "46") (name "Net-(S1-Pad5)") (class "Default")
      (node (ref "S1") (pin "5") (pinfunction "5_5") (pintype "passive"))
      (node (ref "S3") (pin "5") (pinfunction "5_5") (pintype "passive"))
      (node (ref "U$10") (pin "C") (pinfunction "C_C") (pintype "passive"))
    )
    (net (code "47") (name "Net-(S1-Pad6)") (class "Default")
      (node (ref "S1") (pin "6") (pinfunction "6_6") (pintype "passive"))
      (node (ref "S3") (pin "6") (pinfunction "6_6") (pintype "passive"))
      (node (ref "U$9") (pin "C") (pinfunction "C_C") (pintype "passive"))
    )
    (net (code "48") (name "Net-(S1-Pad7)") (class "Default")
      (node (ref "S1") (pin "7") (pinfunction "7_7") (pintype "passive"))
      (node (ref "S3") (pin "7") (pinfunction "7_7") (pintype "passive"))
      (node (ref "U$8") (pin "C") (pinfunction "C_C") (pintype "passive"))
    )
    (net (code "49") (name "Net-(SV1-Pad3)") (class "Default")
      (node (ref "SV1") (pin "3") (pinfunction "3_3") (pintype "passive"))
      (node (ref "U$22") (pin "C") (pinfunction "C_C") (pintype "passive"))
    )
    (net (code "50") (name "Net-(SV1-Pad4)") (class "Default")
      (node (ref "SV1") (pin "4") (pinfunction "4_4") (pintype "passive"))
      (node (ref "U$35") (pin "C") (pinfunction "C_C") (pintype "passive"))
    )
    (net (code "51") (name "Net-(SV1-Pad5)") (class "Default")
      (node (ref "SV1") (pin "5") (pinfunction "5_5") (pintype "passive"))
      (node (ref "U$23") (pin "C") (pinfunction "C_C") (pintype "passive"))
    )
    (net (code "52") (name "Net-(SV1-Pad6)") (class "Default")
      (node (ref "SV1") (pin "6") (pinfunction "6_6") (pintype "passive"))
      (node (ref "U$34") (pin "C") (pinfunction "C_C") (pintype "passive"))
    )
    (net (code "53") (name "Net-(SV1-Pad7)") (class "Default")
      (node (ref "SV1") (pin "7") (pinfunction "7_7") (pintype "passive"))
      (node (ref "U$24") (pin "C") (pinfunction "C_C") (pintype "passive"))
    )
    (net (code "54") (name "Net-(SV1-Pad8)") (class "Default")
      (node (ref "SV1") (pin "8") (pinfunction "8_8") (pintype "passive"))
      (node (ref "U$33") (pin "C") (pinfunction "C_C") (pintype "passive"))
    )
    (net (code "55") (name "Net-(SV1-Pad9)") (class "Default")
      (node (ref "SV1") (pin "9") (pinfunction "9_9") (pintype "passive"))
      (node (ref "U$25") (pin "C") (pinfunction "C_C") (pintype "passive"))
    )
    (net (code "56") (name "Net-(SV1-Pad10)") (class "Default")
      (node (ref "SV1") (pin "10") (pinfunction "10_10") (pintype "passive"))
      (node (ref "U$32") (pin "C") (pinfunction "C_C") (pintype "passive"))
    )
    (net (code "57") (name "Net-(SV1-Pad11)") (class "Default")
      (node (ref "SV1") (pin "11") (pinfunction "11_11") (pintype "passive"))
      (node (ref "U$26") (pin "C") (pinfunction "C_C") (pintype "passive"))
    )
    (net (code "58") (name "Net-(SV1-Pad12)") (class "Default")
      (node (ref "SV1") (pin "12") (pinfunction "12_12") (pintype "passive"))
      (node (ref "U$31") (pin "C") (pinfunction "C_C") (pintype "passive"))
    )
    (net (code "59") (name "Net-(SV1-Pad13)") (class "Default")
      (node (ref "SV1") (pin "13") (pinfunction "13_13") (pintype "passive"))
      (node (ref "U$27") (pin "C") (pinfunction "C_C") (pintype "passive"))
    )
    (net (code "60") (name "Net-(SV1-Pad14)") (class "Default")
      (node (ref "SV1") (pin "14") (pinfunction "14_14") (pintype "passive"))
      (node (ref "U$30") (pin "C") (pinfunction "C_C") (pintype "passive"))
    )
    (net (code "61") (name "Net-(SV1-Pad15)") (class "Default")
      (node (ref "SV1") (pin "15") (pinfunction "15_15") (pintype "passive"))
      (node (ref "U$28") (pin "C") (pinfunction "C_C") (pintype "passive"))
    )
    (net (code "62") (name "Net-(SV1-Pad16)") (class "Default")
      (node (ref "SV1") (pin "16") (pinfunction "16_16") (pintype "passive"))
      (node (ref "U$29") (pin "C") (pinfunction "C_C") (pintype "passive"))
    )
    (net (code "63") (name "Net-(SV2-Pad3)") (class "Default")
      (node (ref "SV2") (pin "3") (pinfunction "3_3") (pintype "passive"))
      (node (ref "U$36") (pin "C") (pinfunction "C_C") (pintype "passive"))
    )
    (net (code "64") (name "Net-(SV2-Pad4)") (class "Default")
      (node (ref "SV2") (pin "4") (pinfunction "4_4") (pintype "passive"))
      (node (ref "U$49") (pin "C") (pinfunction "C_C") (pintype "passive"))
    )
    (net (code "65") (name "Net-(SV2-Pad5)") (class "Default")
      (node (ref "SV2") (pin "5") (pinfunction "5_5") (pintype "passive"))
      (node (ref "U$37") (pin "C") (pinfunction "C_C") (pintype "passive"))
    )
    (net (code "66") (name "Net-(SV2-Pad6)") (class "Default")
      (node (ref "SV2") (pin "6") (pinfunction "6_6") (pintype "passive"))
      (node (ref "U$48") (pin "C") (pinfunction "C_C") (pintype "passive"))
    )
    (net (code "67") (name "Net-(SV2-Pad7)") (class "Default")
      (node (ref "SV2") (pin "7") (pinfunction "7_7") (pintype "passive"))
      (node (ref "U$38") (pin "C") (pinfunction "C_C") (pintype "passive"))
    )
    (net (code "68") (name "Net-(SV2-Pad8)") (class "Default")
      (node (ref "SV2") (pin "8") (pinfunction "8_8") (pintype "passive"))
      (node (ref "U$47") (pin "C") (pinfunction "C_C") (pintype "passive"))
    )
    (net (code "69") (name "Net-(SV2-Pad9)") (class "Default")
      (node (ref "SV2") (pin "9") (pinfunction "9_9") (pintype "passive"))
      (node (ref "U$39") (pin "C") (pinfunction "C_C") (pintype "passive"))
    )
    (net (code "70") (name "Net-(SV2-Pad10)") (class "Default")
      (node (ref "SV2") (pin "10") (pinfunction "10_10") (pintype "passive"))
      (node (ref "U$46") (pin "C") (pinfunction "C_C") (pintype "passive"))
    )
    (net (code "71") (name "Net-(SV2-Pad11)") (class "Default")
      (node (ref "SV2") (pin "11") (pinfunction "11_11") (pintype "passive"))
      (node (ref "U$40") (pin "C") (pinfunction "C_C") (pintype "passive"))
    )
    (net (code "72") (name "Net-(SV2-Pad12)") (class "Default")
      (node (ref "SV2") (pin "12") (pinfunction "12_12") (pintype "passive"))
      (node (ref "U$45") (pin "C") (pinfunction "C_C") (pintype "passive"))
    )
    (net (code "73") (name "Net-(SV2-Pad13)") (class "Default")
      (node (ref "SV2") (pin "13") (pinfunction "13_13") (pintype "passive"))
      (node (ref "U$41") (pin "C") (pinfunction "C_C") (pintype "passive"))
    )
    (net (code "74") (name "Net-(SV2-Pad14)") (class "Default")
      (node (ref "SV2") (pin "14") (pinfunction "14_14") (pintype "passive"))
      (node (ref "U$44") (pin "C") (pinfunction "C_C") (pintype "passive"))
    )
    (net (code "75") (name "Net-(SV2-Pad15)") (class "Default")
      (node (ref "SV2") (pin "15") (pinfunction "15_15") (pintype "passive"))
      (node (ref "U$42") (pin "C") (pinfunction "C_C") (pintype "passive"))
    )
    (net (code "76") (name "Net-(SV2-Pad16)") (class "Default")
      (node (ref "SV2") (pin "16") (pinfunction "16_16") (pintype "passive"))
      (node (ref "U$43") (pin "C") (pinfunction "C_C") (pintype "passive"))
    )
    (net (code "77") (name "Net-(SV3-Pad3)") (class "Default")
      (node (ref "SV3") (pin "3") (pinfunction "3_3") (pintype "passive"))
      (node (ref "U$1") (pin "C") (pinfunction "C_C") (pintype "passive"))
    )
    (net (code "78") (name "Net-(SV3-Pad4)") (class "Default")
      (node (ref "SV3") (pin "4") (pinfunction "4_4") (pintype "passive"))
      (node (ref "U$21") (pin "C") (pinfunction "C_C") (pintype "passive"))
    )
    (net (code "79") (name "Net-(SV3-Pad5)") (class "Default")
      (node (ref "SV3") (pin "5") (pinfunction "5_5") (pintype "passive"))
      (node (ref "U$2") (pin "C") (pinfunction "C_C") (pintype "passive"))
    )
    (net (code "80") (name "Net-(SV3-Pad6)") (class "Default")
      (node (ref "SV3") (pin "6") (pinfunction "6_6") (pintype "passive"))
      (node (ref "U$20") (pin "C") (pinfunction "C_C") (pintype "passive"))
    )
    (net (code "81") (name "Net-(SV3-Pad7)") (class "Default")
      (node (ref "SV3") (pin "7") (pinfunction "7_7") (pintype "passive"))
      (node (ref "U$3") (pin "C") (pinfunction "C_C") (pintype "passive"))
    )
    (net (code "82") (name "Net-(SV3-Pad8)") (class "Default")
      (node (ref "SV3") (pin "8") (pinfunction "8_8") (pintype "passive"))
      (node (ref "U$19") (pin "C") (pinfunction "C_C") (pintype "passive"))
    )
    (net (code "83") (name "Net-(SV3-Pad9)") (class "Default")
      (node (ref "SV3") (pin "9") (pinfunction "9_9") (pintype "passive"))
      (node (ref "U$4") (pin "C") (pinfunction "C_C") (pintype "passive"))
    )
    (net (code "84") (name "Net-(SV3-Pad10)") (class "Default")
      (node (ref "SV3") (pin "10") (pinfunction "10_10") (pintype "passive"))
      (node (ref "U$18") (pin "C") (pinfunction "C_C") (pintype "passive"))
    )
    (net (code "85") (name "Net-(SV3-Pad11)") (class "Default")
      (node (ref "SV3") (pin "11") (pinfunction "11_11") (pintype "passive"))
      (node (ref "U$5") (pin "C") (pinfunction "C_C") (pintype "passive"))
    )
    (net (code "86") (name "Net-(SV3-Pad12)") (class "Default")
      (node (ref "SV3") (pin "12") (pinfunction "12_12") (pintype "passive"))
      (node (ref "U$17") (pin "C") (pinfunction "C_C") (pintype "passive"))
    )
    (net (code "87") (name "Net-(SV3-Pad13)") (class "Default")
      (node (ref "SV3") (pin "13") (pinfunction "13_13") (pintype "passive"))
      (node (ref "U$6") (pin "C") (pinfunction "C_C") (pintype "passive"))
    )
    (net (code "88") (name "Net-(SV3-Pad14)") (class "Default")
      (node (ref "SV3") (pin "14") (pinfunction "14_14") (pintype "passive"))
      (node (ref "U$16") (pin "C") (pinfunction "C_C") (pintype "passive"))
    )
    (net (code "89") (name "Net-(SV3-Pad15)") (class "Default")
      (node (ref "SV3") (pin "15") (pinfunction "15_15") (pintype "passive"))
      (node (ref "U$7") (pin "C") (pinfunction "C_C") (pintype "passive"))
    )
    (net (code "90") (name "Net-(SV3-Pad16)") (class "Default")
      (node (ref "SV3") (pin "16") (pinfunction "16_16") (pintype "passive"))
      (node (ref "U$15") (pin "C") (pinfunction "C_C") (pintype "passive"))
    )
    (net (code "91") (name "Net-(SV4-Pad3)") (class "Default")
      (node (ref "SV4") (pin "3") (pinfunction "3_3") (pintype "passive"))
      (node (ref "U$51") (pin "C") (pinfunction "C_C") (pintype "passive"))
    )
    (net (code "92") (name "Net-(SV4-Pad4)") (class "Default")
      (node (ref "SV4") (pin "4") (pinfunction "4_4") (pintype "passive"))
      (node (ref "U$64") (pin "C") (pinfunction "C_C") (pintype "passive"))
    )
    (net (code "93") (name "Net-(SV4-Pad5)") (class "Default")
      (node (ref "SV4") (pin "5") (pinfunction "5_5") (pintype "passive"))
      (node (ref "U$52") (pin "C") (pinfunction "C_C") (pintype "passive"))
    )
    (net (code "94") (name "Net-(SV4-Pad6)") (class "Default")
      (node (ref "SV4") (pin "6") (pinfunction "6_6") (pintype "passive"))
      (node (ref "U$63") (pin "C") (pinfunction "C_C") (pintype "passive"))
    )
    (net (code "95") (name "Net-(SV4-Pad7)") (class "Default")
      (node (ref "SV4") (pin "7") (pinfunction "7_7") (pintype "passive"))
      (node (ref "U$53") (pin "C") (pinfunction "C_C") (pintype "passive"))
    )
    (net (code "96") (name "Net-(SV4-Pad8)") (class "Default")
      (node (ref "SV4") (pin "8") (pinfunction "8_8") (pintype "passive"))
      (node (ref "U$62") (pin "C") (pinfunction "C_C") (pintype "passive"))
    )
    (net (code "97") (name "Net-(SV4-Pad9)") (class "Default")
      (node (ref "SV4") (pin "9") (pinfunction "9_9") (pintype "passive"))
      (node (ref "U$54") (pin "C") (pinfunction "C_C") (pintype "passive"))
    )
    (net (code "98") (name "Net-(SV4-Pad10)") (class "Default")
      (node (ref "SV4") (pin "10") (pinfunction "10_10") (pintype "passive"))
      (node (ref "U$61") (pin "C") (pinfunction "C_C") (pintype "passive"))
    )
    (net (code "99") (name "Net-(SV4-Pad11)") (class "Default")
      (node (ref "SV4") (pin "11") (pinfunction "11_11") (pintype "passive"))
      (node (ref "U$55") (pin "C") (pinfunction "C_C") (pintype "passive"))
    )
    (net (code "100") (name "Net-(SV4-Pad12)") (class "Default")
      (node (ref "SV4") (pin "12") (pinfunction "12_12") (pintype "passive"))
      (node (ref "U$60") (pin "C") (pinfunction "C_C") (pintype "passive"))
    )
    (net (code "101") (name "Net-(SV4-Pad13)") (class "Default")
      (node (ref "SV4") (pin "13") (pinfunction "13_13") (pintype "passive"))
      (node (ref "U$56") (pin "C") (pinfunction "C_C") (pintype "passive"))
    )
    (net (code "102") (name "Net-(SV4-Pad14)") (class "Default")
      (node (ref "SV4") (pin "14") (pinfunction "14_14") (pintype "passive"))
      (node (ref "U$59") (pin "C") (pinfunction "C_C") (pintype "passive"))
    )
    (net (code "103") (name "Net-(SV4-Pad15)") (class "Default")
      (node (ref "SV4") (pin "15") (pinfunction "15_15") (pintype "passive"))
      (node (ref "U$57") (pin "C") (pinfunction "C_C") (pintype "passive"))
    )
    (net (code "104") (name "Net-(SV4-Pad16)") (class "Default")
      (node (ref "SV4") (pin "16") (pinfunction "16_16") (pintype "passive"))
      (node (ref "U$58") (pin "C") (pinfunction "C_C") (pintype "passive"))
    )
    (net (code "105") (name "Net-(SV7-Pad3)") (class "Default")
      (node (ref "SV7") (pin "3") (pinfunction "3_3") (pintype "passive"))
      (node (ref "U$65") (pin "C") (pinfunction "C_C") (pintype "passive"))
    )
    (net (code "106") (name "Net-(SV7-Pad4)") (class "Default")
      (node (ref "SV7") (pin "4") (pinfunction "4_4") (pintype "passive"))
      (node (ref "U$78") (pin "C") (pinfunction "C_C") (pintype "passive"))
    )
    (net (code "107") (name "Net-(SV7-Pad5)") (class "Default")
      (node (ref "SV7") (pin "5") (pinfunction "5_5") (pintype "passive"))
      (node (ref "U$66") (pin "C") (pinfunction "C_C") (pintype "passive"))
    )
    (net (code "108") (name "Net-(SV7-Pad6)") (class "Default")
      (node (ref "SV7") (pin "6") (pinfunction "6_6") (pintype "passive"))
      (node (ref "U$77") (pin "C") (pinfunction "C_C") (pintype "passive"))
    )
    (net (code "109") (name "Net-(SV7-Pad7)") (class "Default")
      (node (ref "SV7") (pin "7") (pinfunction "7_7") (pintype "passive"))
      (node (ref "U$67") (pin "C") (pinfunction "C_C") (pintype "passive"))
    )
    (net (code "110") (name "Net-(SV7-Pad8)") (class "Default")
      (node (ref "SV7") (pin "8") (pinfunction "8_8") (pintype "passive"))
      (node (ref "U$76") (pin "C") (pinfunction "C_C") (pintype "passive"))
    )
    (net (code "111") (name "Net-(SV7-Pad9)") (class "Default")
      (node (ref "SV7") (pin "9") (pinfunction "9_9") (pintype "passive"))
      (node (ref "U$68") (pin "C") (pinfunction "C_C") (pintype "passive"))
    )
    (net (code "112") (name "Net-(SV7-Pad10)") (class "Default")
      (node (ref "SV7") (pin "10") (pinfunction "10_10") (pintype "passive"))
      (node (ref "U$75") (pin "C") (pinfunction "C_C") (pintype "passive"))
    )
    (net (code "113") (name "Net-(SV7-Pad11)") (class "Default")
      (node (ref "SV7") (pin "11") (pinfunction "11_11") (pintype "passive"))
      (node (ref "U$69") (pin "C") (pinfunction "C_C") (pintype "passive"))
    )
    (net (code "114") (name "Net-(SV7-Pad12)") (class "Default")
      (node (ref "SV7") (pin "12") (pinfunction "12_12") (pintype "passive"))
      (node (ref "U$74") (pin "C") (pinfunction "C_C") (pintype "passive"))
    )
    (net (code "115") (name "Net-(SV7-Pad13)") (class "Default")
      (node (ref "SV7") (pin "13") (pinfunction "13_13") (pintype "passive"))
      (node (ref "U$70") (pin "C") (pinfunction "C_C") (pintype "passive"))
    )
    (net (code "116") (name "Net-(SV7-Pad14)") (class "Default")
      (node (ref "SV7") (pin "14") (pinfunction "14_14") (pintype "passive"))
      (node (ref "U$73") (pin "C") (pinfunction "C_C") (pintype "passive"))
    )
    (net (code "117") (name "Net-(SV7-Pad15)") (class "Default")
      (node (ref "SV7") (pin "15") (pinfunction "15_15") (pintype "passive"))
      (node (ref "U$71") (pin "C") (pinfunction "C_C") (pintype "passive"))
    )
    (net (code "118") (name "Net-(SV7-Pad16)") (class "Default")
      (node (ref "SV7") (pin "16") (pinfunction "16_16") (pintype "passive"))
      (node (ref "U$72") (pin "C") (pinfunction "C_C") (pintype "passive"))
    )
    (net (code "119") (name "Net-(X1D-K)") (class "Default")
      (node (ref "U$50") (pin "A") (pinfunction "A_A") (pintype "passive"))
      (node (ref "X1") (pin "4") (pinfunction "K_4") (pintype "passive"))
    )
    (net (code "120") (name "VCC") (class "Default")
      (node (ref "C3") (pin "1") (pinfunction "1_1") (pintype "passive"))
      (node (ref "C4") (pin "1") (pinfunction "1_1") (pintype "passive"))
      (node (ref "C5") (pin "1") (pinfunction "1_1") (pintype "passive"))
      (node (ref "C7") (pin "1") (pinfunction "1_1") (pintype "passive"))
      (node (ref "C8") (pin "1") (pinfunction "1_1") (pintype "passive"))
      (node (ref "IC1") (pin "1") (pinfunction "ST_1") (pintype "input"))
      (node (ref "IC1") (pin "24") (pinfunction "VDD_24") (pintype "power_in"))
      (node (ref "IC2") (pin "14") (pinfunction "VDD_14") (pintype "power_in"))
      (node (ref "IC4") (pin "1") (pinfunction "VOUT_1") (pintype "output"))
      (node (ref "LED2") (pin "A") (pinfunction "A_A") (pintype "passive"))
      (node (ref "R1") (pin "2") (pinfunction "2_2") (pintype "passive"))
      (node (ref "R2") (pin "2") (pinfunction "2_2") (pintype "passive"))
      (node (ref "T1") (pin "E") (pinfunction "E_E") (pintype "passive"))
    )
  )
)
